# Main.net
KiCad netlist of a schematic drawn in Altium Designer
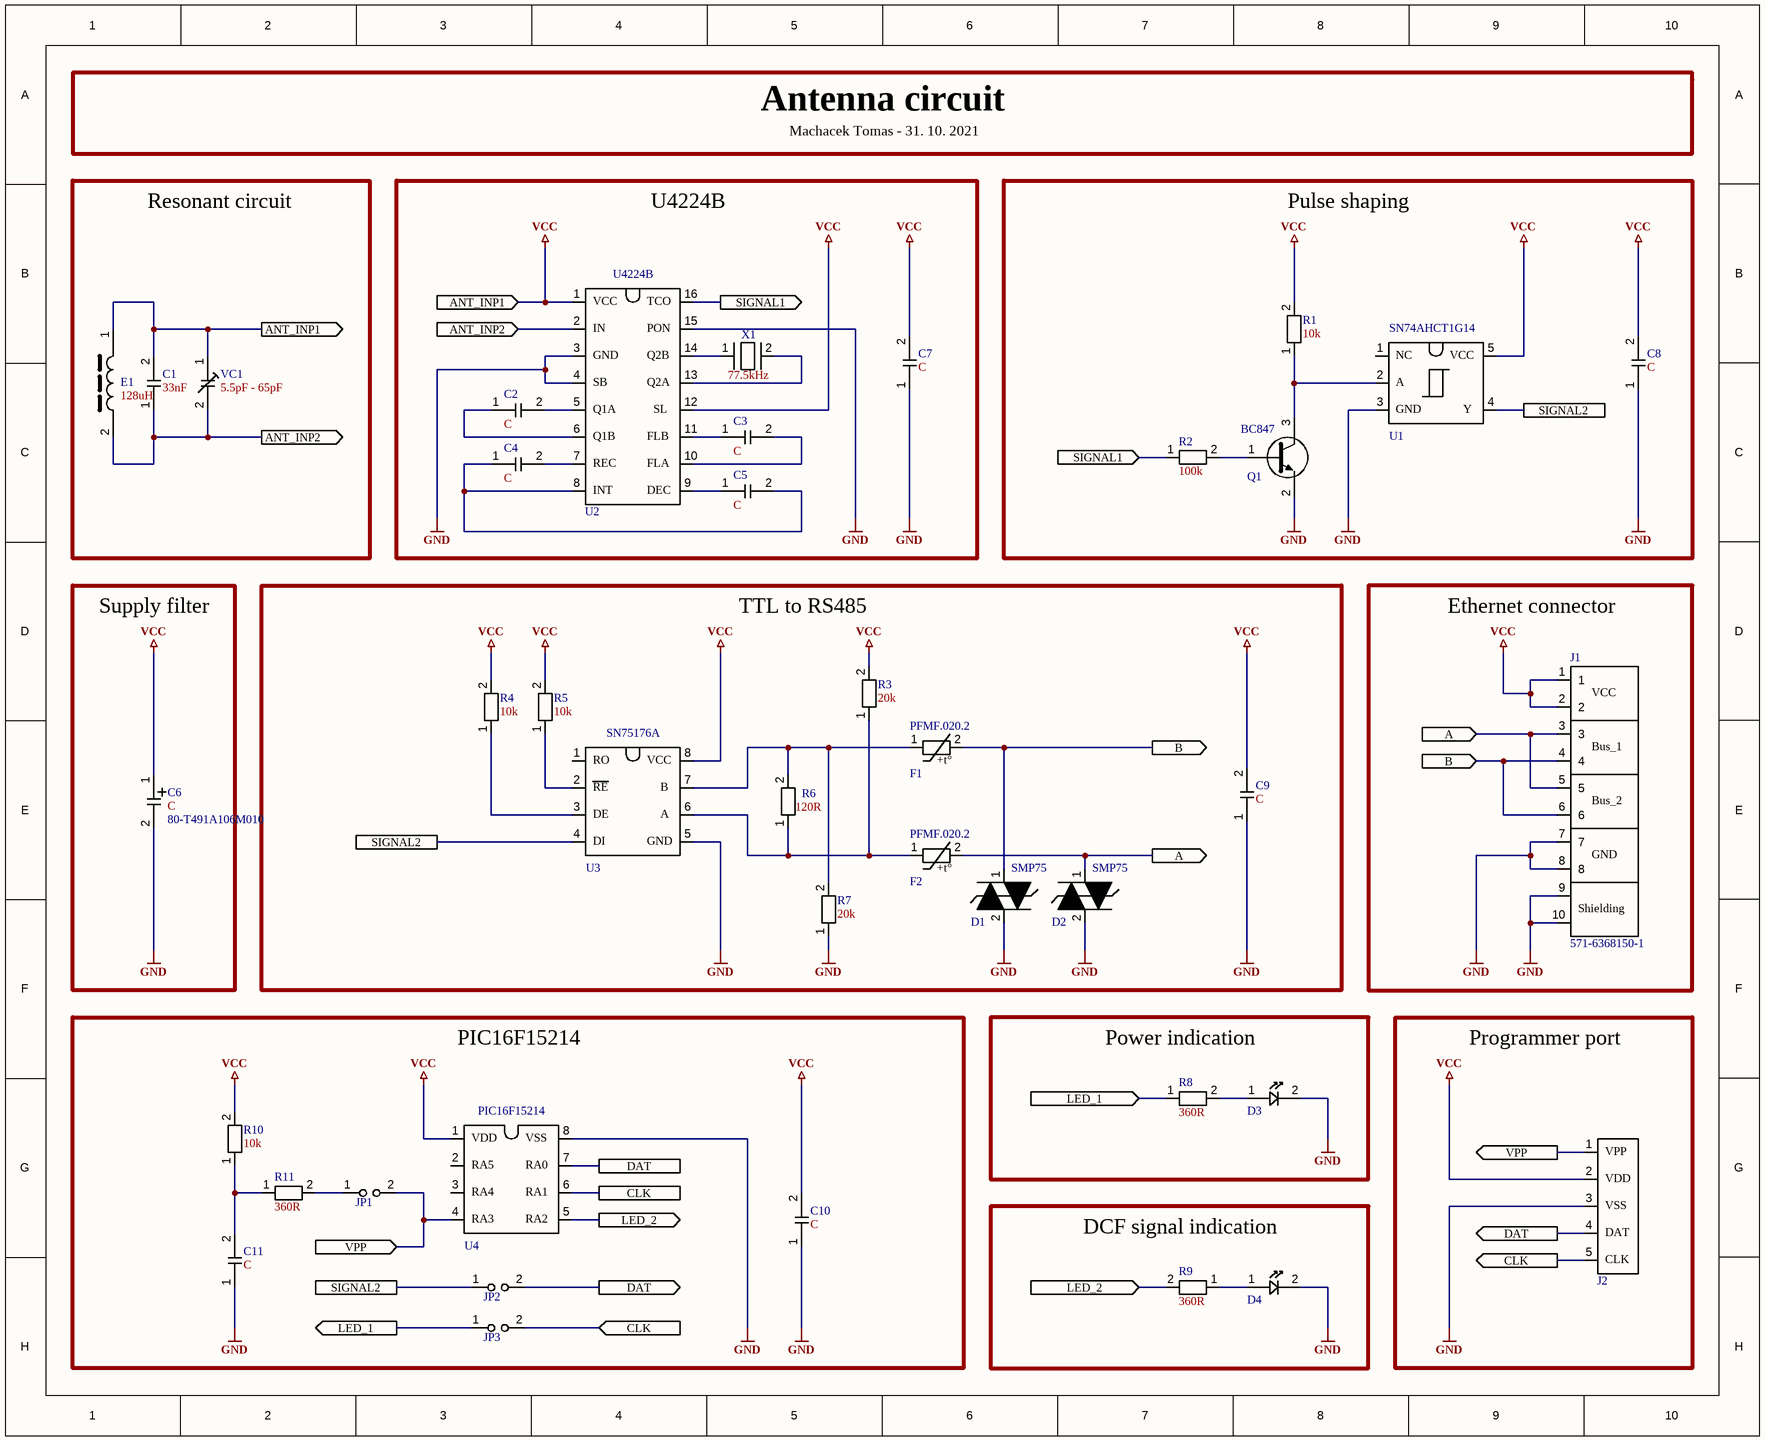
[diagram p0: Main.SchDoc]

(export (version "E")
  (design (tool "Eeschema 10.0.6"))
  (components
    (comp (ref "C1")
      (value "33nF")
      (footprint "Film_capacitator")
      (description "Film capacitator")
      (fields (field (name "Comment") "Capacitator_film"))
      (libsource (lib "Schematic_library") (part "Capacitator_film"))
    )
    (comp (ref "C2")
      (value "C")
      (footprint "MLCC_capacitator")
      (description "MLCC capacitator - 1206")
      (fields (field (name "Comment") "Capacitator_MLCC"))
      (libsource (lib "Schematic_library") (part "Capacitator_MLCC"))
    )
    (comp (ref "C3")
      (value "C")
      (footprint "MLCC_capacitator")
      (description "MLCC capacitator - 1206")
      (fields (field (name "Comment") "Capacitator_MLCC"))
      (libsource (lib "Schematic_library") (part "Capacitator_MLCC"))
    )
    (comp (ref "C4")
      (value "C")
      (footprint "MLCC_capacitator")
      (description "MLCC capacitator - 1206")
      (fields (field (name "Comment") "Capacitator_MLCC"))
      (libsource (lib "Schematic_library") (part "Capacitator_MLCC"))
    )
    (comp (ref "C5")
      (value "C")
      (footprint "MLCC_capacitator")
      (description "MLCC capacitator - 1206")
      (fields (field (name "Comment") "Capacitator_MLCC"))
      (libsource (lib "Schematic_library") (part "Capacitator_MLCC"))
    )
    (comp (ref "C6")
      (value "C")
      (footprint "Tantalum_capacitor")
      (description "Aluminum capacitator - filtration")
      (fields
        (field (name "SUPPLIER PART NUMBER 1") "80-T491A106M010")
        (field (name "Comment") "Capacitator_aluminium")
      )
      (libsource (lib "Schematic_library") (part "Capacitator_aluminium"))
    )
    (comp (ref "C7")
      (value "C")
      (footprint "MLCC_capacitator")
      (description "MLCC capacitator - 1206")
      (fields (field (name "Comment") "Capacitator_MLCC"))
      (libsource (lib "Schematic_library") (part "Capacitator_MLCC"))
    )
    (comp (ref "C8")
      (value "C")
      (footprint "MLCC_capacitator")
      (description "MLCC capacitator - 1206")
      (fields (field (name "Comment") "Capacitator_MLCC"))
      (libsource (lib "Schematic_library") (part "Capacitator_MLCC"))
    )
    (comp (ref "C9")
      (value "C")
      (footprint "MLCC_capacitator")
      (description "MLCC capacitator - 1206")
      (fields (field (name "Comment") "Capacitator_MLCC"))
      (libsource (lib "Schematic_library") (part "Capacitator_MLCC"))
    )
    (comp (ref "C10")
      (value "C")
      (footprint "MLCC_capacitator")
      (description "MLCC capacitator - 1206")
      (fields (field (name "Comment") "Capacitator_MLCC"))
      (libsource (lib "Schematic_library") (part "Capacitator_MLCC"))
    )
    (comp (ref "C11")
      (value "C")
      (footprint "MLCC_capacitator")
      (description "MLCC capacitator - 1206")
      (fields (field (name "Comment") "Capacitator_MLCC"))
      (libsource (lib "Schematic_library") (part "Capacitator_MLCC"))
    )
    (comp (ref "D1")
      (value "SMP75")
      (footprint "SMP75")
      (description "Bidirectional crowbar protection")
      (libsource (lib "Schematic_library") (part "SMP75"))
    )
    (comp (ref "D2")
      (value "SMP75")
      (footprint "SMP75")
      (description "Bidirectional crowbar protection")
      (libsource (lib "Schematic_library") (part "SMP75"))
    )
    (comp (ref "D3")
      (value "Indication_led")
      (footprint "indication_led")
      (description "Indication led to panel")
      (libsource (lib "Schematic_library") (part "Indication_led"))
    )
    (comp (ref "D4")
      (value "Indication_led")
      (footprint "indication_led")
      (description "Indication led to panel")
      (libsource (lib "Schematic_library") (part "Indication_led"))
    )
    (comp (ref "E1")
      (value "128uH")
      (footprint "Antenna")
      (description "Ferrite antenna")
      (fields (field (name "Comment") "Ferrite_antenna"))
      (libsource (lib "Schematic_library") (part "Ferrite_antenna"))
    )
    (comp (ref "F1")
      (value "PFMF.020.2")
      (footprint "PFMF.020.2")
      (description "SMD fuse")
      (libsource (lib "Schematic_library") (part "PFMF.020.2"))
    )
    (comp (ref "F2")
      (value "PFMF.020.2")
      (footprint "PFMF.020.2")
      (description "SMD fuse")
      (libsource (lib "Schematic_library") (part "PFMF.020.2"))
    )
    (comp (ref "J1")
      (value "Ethernet_connector")
      (footprint "Ethernet_connector")
      (description "Ethernet connector")
      (fields (field (name "SUPPLIER PART NUMBER 1") "571-6368150-1"))
      (libsource (lib "Schematic_library") (part "Ethernet_connector"))
    )
    (comp (ref "J2")
      (value "Programmer_port")
      (footprint "Programmer_port")
      (description "Programmer port for PIC")
      (libsource (lib "Schematic_library") (part "Programmer_port"))
    )
    (comp (ref "JP1")
      (value "Jumper")
      (footprint "Jumper")
      (description "Solderable jumper")
      (libsource (lib "Schematic_library") (part "Jumper"))
    )
    (comp (ref "JP2")
      (value "Jumper")
      (footprint "Jumper")
      (description "Solderable jumper")
      (libsource (lib "Schematic_library") (part "Jumper"))
    )
    (comp (ref "JP3")
      (value "Jumper")
      (footprint "Jumper")
      (description "Solderable jumper")
      (libsource (lib "Schematic_library") (part "Jumper"))
    )
    (comp (ref "Q1")
      (value "BC847")
      (footprint "BC847")
      (description "NPN transistor")
      (libsource (lib "Schematic_library") (part "BC847"))
    )
    (comp (ref "R1")
      (value "10k")
      (footprint "Resistor")
      (description "SMD resistor - 1206")
      (fields (field (name "Comment") "Resistor"))
      (libsource (lib "Schematic_library") (part "Resistor"))
    )
    (comp (ref "R2")
      (value "100k")
      (footprint "Resistor")
      (description "SMD resistor - 1206")
      (fields (field (name "Comment") "Resistor"))
      (libsource (lib "Schematic_library") (part "Resistor"))
    )
    (comp (ref "R3")
      (value "20k")
      (footprint "Resistor")
      (description "SMD resistor - 1206")
      (fields (field (name "Comment") "Resistor"))
      (libsource (lib "Schematic_library") (part "Resistor"))
    )
    (comp (ref "R4")
      (value "10k")
      (footprint "Resistor")
      (description "SMD resistor - 1206")
      (fields (field (name "Comment") "Resistor"))
      (libsource (lib "Schematic_library") (part "Resistor"))
    )
    (comp (ref "R5")
      (value "10k")
      (footprint "Resistor")
      (description "SMD resistor - 1206")
      (fields (field (name "Comment") "Resistor"))
      (libsource (lib "Schematic_library") (part "Resistor"))
    )
    (comp (ref "R6")
      (value "120R")
      (footprint "Resistor")
      (description "SMD resistor - 1206")
      (fields (field (name "Comment") "Resistor"))
      (libsource (lib "Schematic_library") (part "Resistor"))
    )
    (comp (ref "R7")
      (value "20k")
      (footprint "Resistor")
      (description "SMD resistor - 1206")
      (fields (field (name "Comment") "Resistor"))
      (libsource (lib "Schematic_library") (part "Resistor"))
    )
    (comp (ref "R8")
      (value "360R")
      (footprint "Resistor")
      (description "SMD resistor - 1206")
      (fields (field (name "Comment") "Resistor"))
      (libsource (lib "Schematic_library") (part "Resistor"))
    )
    (comp (ref "R9")
      (value "360R")
      (footprint "Resistor")
      (description "SMD resistor - 1206")
      (fields (field (name "Comment") "Resistor"))
      (libsource (lib "Schematic_library") (part "Resistor"))
    )
    (comp (ref "R10")
      (value "10k")
      (footprint "Resistor")
      (description "SMD resistor - 1206")
      (fields (field (name "Comment") "Resistor"))
      (libsource (lib "Schematic_library") (part "Resistor"))
    )
    (comp (ref "R11")
      (value "360R")
      (footprint "Resistor")
      (description "SMD resistor - 1206")
      (fields (field (name "Comment") "Resistor"))
      (libsource (lib "Schematic_library") (part "Resistor"))
    )
    (comp (ref "U1")
      (value "SN74AHCT1G14")
      (footprint "SN74AHCT1G14")
      (description "SINGLE SCHMITT-TRIGGER INVERTER GATE")
      (libsource (lib "Schematic_library") (part "SN74AHCT1G14"))
    )
    (comp (ref "U2")
      (value "U4224B")
      (footprint "U422B")
      (description "DCF77 signal decoder")
      (libsource (lib "Schematic_library") (part "U4224B"))
    )
    (comp (ref "U3")
      (value "SN75176A")
      (footprint "SN75176A")
      (description "RS485 transreciever")
      (libsource (lib "Schematic_library") (part "SN75176A"))
    )
    (comp (ref "U4")
      (value "PIC16F15214")
      (footprint "PIC16F15214")
      (description "8-bit microcontroller")
      (libsource (lib "Schematic_library") (part "PIC16F15214"))
    )
    (comp (ref "VC1")
      (value "5.5pF - 65pF")
      (footprint "Trimmer_capacitator")
      (description "Film dielectric trimmer")
      (fields (field (name "Comment") "Trimmer_capacitor"))
      (libsource (lib "Schematic_library") (part "Trimmer_capacitator"))
    )
    (comp (ref "X1")
      (value "77.5kHz")
      (footprint "Crystal")
      (description "Quartz crystal")
      (fields (field (name "Comment") "Crystal"))
      (libsource (lib "Schematic_library") (part "Crystal"))
    )
  )
  (nets
    (net (code "1") (name "/A") (class "Default")
      (node (ref "D2") (pin "1") (pinfunction "1_1") (pintype "passive"))
      (node (ref "F2") (pin "2") (pinfunction "2_2") (pintype "passive"))
      (node (ref "J1") (pin "3") (pinfunction "3_3") (pintype "passive"))
      (node (ref "J1") (pin "5") (pinfunction "5_5") (pintype "passive"))
    )
    (net (code "2") (name "/ANT_INP2") (class "Default")
      (node (ref "C1") (pin "1") (pinfunction "1_1") (pintype "passive"))
      (node (ref "E1") (pin "2") (pinfunction "2_2") (pintype "passive"))
      (node (ref "U2") (pin "2") (pinfunction "2_2") (pintype "passive"))
      (node (ref "VC1") (pin "2") (pinfunction "2_2") (pintype "passive"))
    )
    (net (code "3") (name "/B") (class "Default")
      (node (ref "D1") (pin "1") (pinfunction "1_1") (pintype "passive"))
      (node (ref "F1") (pin "2") (pinfunction "2_2") (pintype "passive"))
      (node (ref "J1") (pin "4") (pinfunction "4_4") (pintype "passive"))
      (node (ref "J1") (pin "6") (pinfunction "6_6") (pintype "passive"))
    )
    (net (code "4") (name "/CLK") (class "Default")
      (node (ref "J2") (pin "5") (pinfunction "5_5") (pintype "passive"))
      (node (ref "JP3") (pin "2") (pinfunction "2_2") (pintype "passive"))
      (node (ref "U4") (pin "6") (pinfunction "6_6") (pintype "passive"))
    )
    (net (code "5") (name "/DAT") (class "Default")
      (node (ref "J2") (pin "4") (pinfunction "4_4") (pintype "passive"))
      (node (ref "JP2") (pin "2") (pinfunction "2_2") (pintype "passive"))
      (node (ref "U4") (pin "7") (pinfunction "7_7") (pintype "passive"))
    )
    (net (code "6") (name "/LED_1") (class "Default")
      (node (ref "JP3") (pin "1") (pinfunction "1_1") (pintype "passive"))
      (node (ref "R8") (pin "1") (pinfunction "1_1") (pintype "passive"))
    )
    (net (code "7") (name "/LED_2") (class "Default")
      (node (ref "R9") (pin "2") (pinfunction "2_2") (pintype "passive"))
      (node (ref "U4") (pin "5") (pinfunction "5_5") (pintype "passive"))
    )
    (net (code "8") (name "/SIGNAL1") (class "Default")
      (node (ref "R2") (pin "1") (pinfunction "1_1") (pintype "passive"))
      (node (ref "U2") (pin "16") (pinfunction "16_16") (pintype "passive"))
    )
    (net (code "9") (name "/SIGNAL2") (class "Default")
      (node (ref "JP2") (pin "1") (pinfunction "1_1") (pintype "passive"))
      (node (ref "U1") (pin "4") (pinfunction "4_4") (pintype "passive"))
      (node (ref "U3") (pin "4") (pinfunction "4_4") (pintype "passive"))
    )
    (net (code "10") (name "/VPP") (class "Default")
      (node (ref "J2") (pin "1") (pinfunction "1_1") (pintype "passive"))
      (node (ref "JP1") (pin "2") (pinfunction "2_2") (pintype "passive"))
      (node (ref "U4") (pin "4") (pinfunction "4_4") (pintype "passive"))
    )
    (net (code "11") (name "GND") (class "Default")
      (node (ref "C10") (pin "1") (pinfunction "1_1") (pintype "passive"))
      (node (ref "C11") (pin "1") (pinfunction "1_1") (pintype "passive"))
      (node (ref "C6") (pin "2") (pinfunction "2_2") (pintype "passive"))
      (node (ref "C7") (pin "1") (pinfunction "1_1") (pintype "passive"))
      (node (ref "C8") (pin "1") (pinfunction "1_1") (pintype "passive"))
      (node (ref "C9") (pin "1") (pinfunction "1_1") (pintype "passive"))
      (node (ref "D1") (pin "2") (pinfunction "2_2") (pintype "passive"))
      (node (ref "D2") (pin "2") (pinfunction "2_2") (pintype "passive"))
      (node (ref "D3") (pin "2") (pinfunction "2_2") (pintype "passive"))
      (node (ref "D4") (pin "2") (pinfunction "2_2") (pintype "passive"))
      (node (ref "J1") (pin "10") (pinfunction "10_10") (pintype "passive"))
      (node (ref "J1") (pin "7") (pinfunction "7_7") (pintype "passive"))
      (node (ref "J1") (pin "8") (pinfunction "8_8") (pintype "passive"))
      (node (ref "J1") (pin "9") (pinfunction "9_9") (pintype "passive"))
      (node (ref "J2") (pin "3") (pinfunction "3_3") (pintype "passive"))
      (node (ref "Q1") (pin "2") (pinfunction "2_2") (pintype "passive"))
      (node (ref "R7") (pin "1") (pinfunction "1_1") (pintype "passive"))
      (node (ref "U1") (pin "3") (pinfunction "3_3") (pintype "passive"))
      (node (ref "U2") (pin "15") (pinfunction "15_15") (pintype "passive"))
      (node (ref "U2") (pin "3") (pinfunction "3_3") (pintype "passive"))
      (node (ref "U2") (pin "4") (pinfunction "4_4") (pintype "passive"))
      (node (ref "U3") (pin "5") (pinfunction "5_5") (pintype "passive"))
      (node (ref "U4") (pin "8") (pinfunction "8_8") (pintype "passive"))
    )
    (net (code "12") (name "Net-(C2-Pad1)") (class "Default")
      (node (ref "C2") (pin "1") (pinfunction "1_1") (pintype "passive"))
      (node (ref "U2") (pin "6") (pinfunction "6_6") (pintype "passive"))
    )
    (net (code "13") (name "Net-(C2-Pad2)") (class "Default")
      (node (ref "C2") (pin "2") (pinfunction "2_2") (pintype "passive"))
      (node (ref "U2") (pin "5") (pinfunction "5_5") (pintype "passive"))
    )
    (net (code "14") (name "Net-(C3-Pad1)") (class "Default")
      (node (ref "C3") (pin "1") (pinfunction "1_1") (pintype "passive"))
      (node (ref "U2") (pin "11") (pinfunction "11_11") (pintype "passive"))
    )
    (net (code "15") (name "Net-(C3-Pad2)") (class "Default")
      (node (ref "C3") (pin "2") (pinfunction "2_2") (pintype "passive"))
      (node (ref "U2") (pin "10") (pinfunction "10_10") (pintype "passive"))
    )
    (net (code "16") (name "Net-(C4-Pad1)") (class "Default")
      (node (ref "C4") (pin "1") (pinfunction "1_1") (pintype "passive"))
      (node (ref "C5") (pin "2") (pinfunction "2_2") (pintype "passive"))
      (node (ref "U2") (pin "8") (pinfunction "8_8") (pintype "passive"))
    )
    (net (code "17") (name "Net-(C4-Pad2)") (class "Default")
      (node (ref "C4") (pin "2") (pinfunction "2_2") (pintype "passive"))
      (node (ref "U2") (pin "7") (pinfunction "7_7") (pintype "passive"))
    )
    (net (code "18") (name "Net-(C5-Pad1)") (class "Default")
      (node (ref "C5") (pin "1") (pinfunction "1_1") (pintype "passive"))
      (node (ref "U2") (pin "9") (pinfunction "9_9") (pintype "passive"))
    )
    (net (code "19") (name "Net-(C11-Pad2)") (class "Default")
      (node (ref "C11") (pin "2") (pinfunction "2_2") (pintype "passive"))
      (node (ref "R10") (pin "1") (pinfunction "1_1") (pintype "passive"))
      (node (ref "R11") (pin "1") (pinfunction "1_1") (pintype "passive"))
    )
    (net (code "20") (name "Net-(D3-Pad1)") (class "Default")
      (node (ref "D3") (pin "1") (pinfunction "1_1") (pintype "passive"))
      (node (ref "R8") (pin "2") (pinfunction "2_2") (pintype "passive"))
    )
    (net (code "21") (name "Net-(D4-Pad1)") (class "Default")
      (node (ref "D4") (pin "1") (pinfunction "1_1") (pintype "passive"))
      (node (ref "R9") (pin "1") (pinfunction "1_1") (pintype "passive"))
    )
    (net (code "22") (name "Net-(F1-Pad1)") (class "Default")
      (node (ref "F1") (pin "1") (pinfunction "1_1") (pintype "passive"))
      (node (ref "R6") (pin "2") (pinfunction "2_2") (pintype "passive"))
      (node (ref "R7") (pin "2") (pinfunction "2_2") (pintype "passive"))
      (node (ref "U3") (pin "7") (pinfunction "7_7") (pintype "passive"))
    )
    (net (code "23") (name "Net-(F2-Pad1)") (class "Default")
      (node (ref "F2") (pin "1") (pinfunction "1_1") (pintype "passive"))
      (node (ref "R3") (pin "1") (pinfunction "1_1") (pintype "passive"))
      (node (ref "R6") (pin "1") (pinfunction "1_1") (pintype "passive"))
      (node (ref "U3") (pin "6") (pinfunction "6_6") (pintype "passive"))
    )
    (net (code "24") (name "Net-(JP1-Pad1)") (class "Default")
      (node (ref "JP1") (pin "1") (pinfunction "1_1") (pintype "passive"))
      (node (ref "R11") (pin "2") (pinfunction "2_2") (pintype "passive"))
    )
    (net (code "25") (name "Net-(Q1-Pad1)") (class "Default")
      (node (ref "Q1") (pin "1") (pinfunction "1_1") (pintype "passive"))
      (node (ref "R2") (pin "2") (pinfunction "2_2") (pintype "passive"))
    )
    (net (code "26") (name "Net-(Q1-Pad3)") (class "Default")
      (node (ref "Q1") (pin "3") (pinfunction "3_3") (pintype "passive"))
      (node (ref "R1") (pin "1") (pinfunction "1_1") (pintype "passive"))
      (node (ref "U1") (pin "2") (pinfunction "2_2") (pintype "passive"))
    )
    (net (code "27") (name "Net-(R4-Pad1)") (class "Default")
      (node (ref "R4") (pin "1") (pinfunction "1_1") (pintype "passive"))
      (node (ref "U3") (pin "3") (pinfunction "3_3") (pintype "passive"))
    )
    (net (code "28") (name "Net-(R5-Pad1)") (class "Default")
      (node (ref "R5") (pin "1") (pinfunction "1_1") (pintype "passive"))
      (node (ref "U3") (pin "2") (pinfunction "2_2") (pintype "passive"))
    )
    (net (code "29") (name "Net-(U2-Pad13)") (class "Default")
      (node (ref "U2") (pin "13") (pinfunction "13_13") (pintype "passive"))
      (node (ref "X1") (pin "2") (pinfunction "2_2") (pintype "passive"))
    )
    (net (code "30") (name "Net-(U2-Pad14)") (class "Default")
      (node (ref "U2") (pin "14") (pinfunction "14_14") (pintype "passive"))
      (node (ref "X1") (pin "1") (pinfunction "1_1") (pintype "passive"))
    )
    (net (code "31") (name "VCC") (class "Default")
      (node (ref "C1") (pin "2") (pinfunction "2_2") (pintype "passive"))
      (node (ref "C10") (pin "2") (pinfunction "2_2") (pintype "passive"))
      (node (ref "C6") (pin "1") (pinfunction "1_1") (pintype "passive"))
      (node (ref "C7") (pin "2") (pinfunction "2_2") (pintype "passive"))
      (node (ref "C8") (pin "2") (pinfunction "2_2") (pintype "passive"))
      (node (ref "C9") (pin "2") (pinfunction "2_2") (pintype "passive"))
      (node (ref "E1") (pin "1") (pinfunction "1_1") (pintype "passive"))
      (node (ref "J1") (pin "1") (pinfunction "1_1") (pintype "passive"))
      (node (ref "J1") (pin "2") (pinfunction "2_2") (pintype "passive"))
      (node (ref "J2") (pin "2") (pinfunction "2_2") (pintype "passive"))
      (node (ref "R1") (pin "2") (pinfunction "2_2") (pintype "passive"))
      (node (ref "R10") (pin "2") (pinfunction "2_2") (pintype "passive"))
      (node (ref "R3") (pin "2") (pinfunction "2_2") (pintype "passive"))
      (node (ref "R4") (pin "2") (pinfunction "2_2") (pintype "passive"))
      (node (ref "R5") (pin "2") (pinfunction "2_2") (pintype "passive"))
      (node (ref "U1") (pin "5") (pinfunction "5_5") (pintype "passive"))
      (node (ref "U2") (pin "1") (pinfunction "1_1") (pintype "passive"))
      (node (ref "U2") (pin "12") (pinfunction "12_12") (pintype "passive"))
      (node (ref "U3") (pin "8") (pinfunction "8_8") (pintype "passive"))
      (node (ref "U4") (pin "1") (pinfunction "1_1") (pintype "passive"))
      (node (ref "VC1") (pin "1") (pinfunction "1_1") (pintype "passive"))
    )
    (net (code "32") (name "unconnected-(U1-Pad1)") (class "Default")
      (node (ref "U1") (pin "1") (pinfunction "1_1") (pintype "passive"))
    )
    (net (code "33") (name "unconnected-(U3-Pad1)") (class "Default")
      (node (ref "U3") (pin "1") (pinfunction "1_1") (pintype "passive"))
    )
    (net (code "34") (name "unconnected-(U4-Pad2)") (class "Default")
      (node (ref "U4") (pin "2") (pinfunction "2_2") (pintype "passive"))
    )
    (net (code "35") (name "unconnected-(U4-Pad3)") (class "Default")
      (node (ref "U4") (pin "3") (pinfunction "3_3") (pintype "passive"))
    )
  )
)
